# LPCB235_-_IO_Connector.net
KiCad netlist of a schematic drawn in Altium Designer
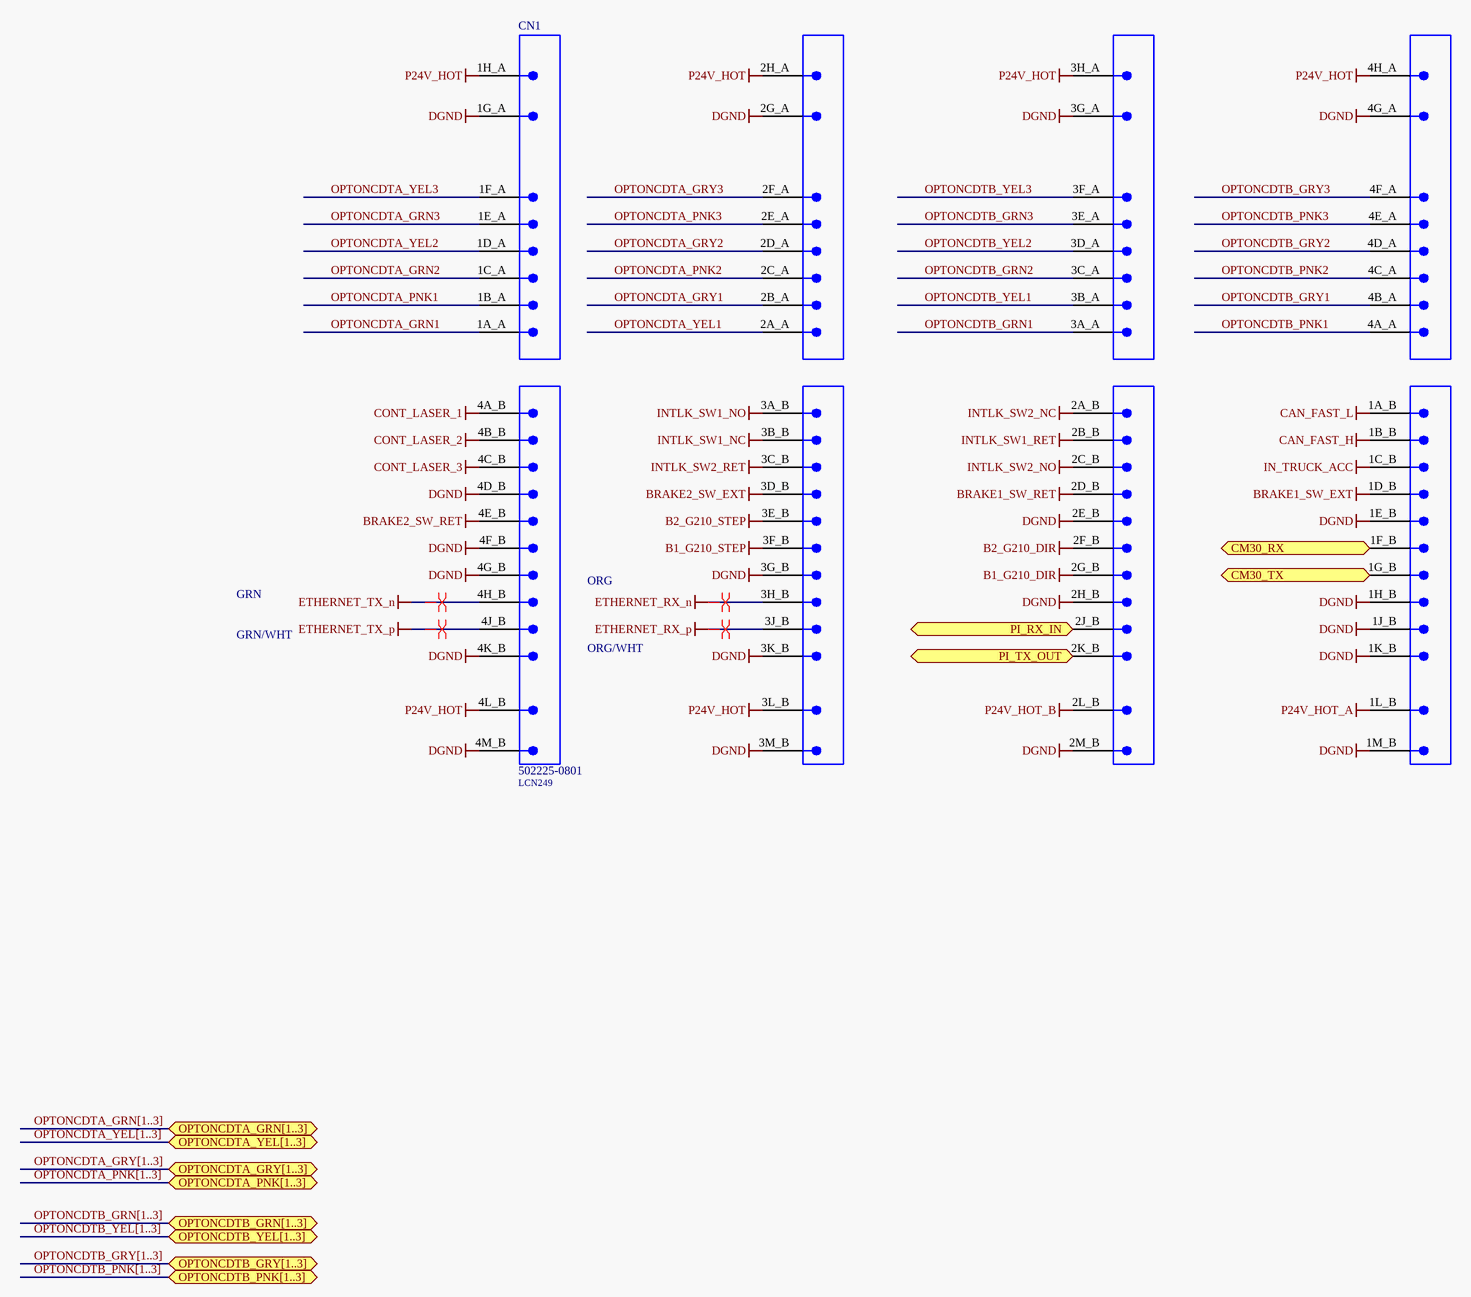
[diagram p0: LPCB235 - IO Connector.SchDoc]

(export (version "E")
  (design (tool "Eeschema 10.0.6"))
  (components
    (comp (ref "CN1")
      (value "502225-0801")
      (footprint "502225-0801")
      (description "Connector, Molex CMC, Automotive Socket, 80 Circuits, 2 Pockets")
      (fields (field (name "LDL_NUMBER") "LCN249"))
      (libsource (lib "LDL_Connectors") (part "502225-0801"))
    )
  )
  (nets
    (net (code "1") (name "/CM30_RX") (class "Default")
      (node (ref "CN1") (pin "1F_B") (pinfunction "1F_B_1F_B") (pintype "passive"))
    )
    (net (code "2") (name "/CM30_TX") (class "Default")
      (node (ref "CN1") (pin "1G_B") (pinfunction "1G_B_1G_B") (pintype "passive"))
    )
    (net (code "3") (name "/OPTONCDTA_GRN1") (class "Default")
      (node (ref "CN1") (pin "1A_A") (pinfunction "1A_1A_A") (pintype "passive"))
    )
    (net (code "4") (name "/OPTONCDTA_GRN2") (class "Default")
      (node (ref "CN1") (pin "1C_A") (pinfunction "1C_1C_A") (pintype "passive"))
    )
    (net (code "5") (name "/OPTONCDTA_GRN3") (class "Default")
      (node (ref "CN1") (pin "1E_A") (pinfunction "1E_1E_A") (pintype "passive"))
    )
    (net (code "7") (name "/OPTONCDTA_GRY1") (class "Default")
      (node (ref "CN1") (pin "2B_A") (pinfunction "2B_2B_A") (pintype "passive"))
    )
    (net (code "8") (name "/OPTONCDTA_GRY2") (class "Default")
      (node (ref "CN1") (pin "2D_A") (pinfunction "2D_2D_A") (pintype "passive"))
    )
    (net (code "9") (name "/OPTONCDTA_GRY3") (class "Default")
      (node (ref "CN1") (pin "2F_A") (pinfunction "2F_2F_A") (pintype "passive"))
    )
    (net (code "11") (name "/OPTONCDTA_PNK1") (class "Default")
      (node (ref "CN1") (pin "1B_A") (pinfunction "1B_1B_A") (pintype "passive"))
    )
    (net (code "12") (name "/OPTONCDTA_PNK2") (class "Default")
      (node (ref "CN1") (pin "2C_A") (pinfunction "2C_2C_A") (pintype "passive"))
    )
    (net (code "13") (name "/OPTONCDTA_PNK3") (class "Default")
      (node (ref "CN1") (pin "2E_A") (pinfunction "2E_2E_A") (pintype "passive"))
    )
    (net (code "15") (name "/OPTONCDTA_YEL1") (class "Default")
      (node (ref "CN1") (pin "2A_A") (pinfunction "2A_2A_A") (pintype "passive"))
    )
    (net (code "16") (name "/OPTONCDTA_YEL2") (class "Default")
      (node (ref "CN1") (pin "1D_A") (pinfunction "1D_1D_A") (pintype "passive"))
    )
    (net (code "17") (name "/OPTONCDTA_YEL3") (class "Default")
      (node (ref "CN1") (pin "1F_A") (pinfunction "1F_1F_A") (pintype "passive"))
    )
    (net (code "19") (name "/OPTONCDTB_GRN1") (class "Default")
      (node (ref "CN1") (pin "3A_A") (pinfunction "3A_3A_A") (pintype "passive"))
    )
    (net (code "20") (name "/OPTONCDTB_GRN2") (class "Default")
      (node (ref "CN1") (pin "3C_A") (pinfunction "3C_3C_A") (pintype "passive"))
    )
    (net (code "21") (name "/OPTONCDTB_GRN3") (class "Default")
      (node (ref "CN1") (pin "3E_A") (pinfunction "3E_3E_A") (pintype "passive"))
    )
    (net (code "23") (name "/OPTONCDTB_GRY1") (class "Default")
      (node (ref "CN1") (pin "4B_A") (pinfunction "4B_4B_A") (pintype "passive"))
    )
    (net (code "24") (name "/OPTONCDTB_GRY2") (class "Default")
      (node (ref "CN1") (pin "4D_A") (pinfunction "4D_4D_A") (pintype "passive"))
    )
    (net (code "25") (name "/OPTONCDTB_GRY3") (class "Default")
      (node (ref "CN1") (pin "4F_A") (pinfunction "4F_4F_A") (pintype "passive"))
    )
    (net (code "27") (name "/OPTONCDTB_PNK1") (class "Default")
      (node (ref "CN1") (pin "4A_A") (pinfunction "4A_4A_A") (pintype "passive"))
    )
    (net (code "28") (name "/OPTONCDTB_PNK2") (class "Default")
      (node (ref "CN1") (pin "4C_A") (pinfunction "4C_4C_A") (pintype "passive"))
    )
    (net (code "29") (name "/OPTONCDTB_PNK3") (class "Default")
      (node (ref "CN1") (pin "4E_A") (pinfunction "4E_4E_A") (pintype "passive"))
    )
    (net (code "31") (name "/OPTONCDTB_YEL1") (class "Default")
      (node (ref "CN1") (pin "3B_A") (pinfunction "3B_3B_A") (pintype "passive"))
    )
    (net (code "32") (name "/OPTONCDTB_YEL2") (class "Default")
      (node (ref "CN1") (pin "3D_A") (pinfunction "3D_3D_A") (pintype "passive"))
    )
    (net (code "33") (name "/OPTONCDTB_YEL3") (class "Default")
      (node (ref "CN1") (pin "3F_A") (pinfunction "3F_3F_A") (pintype "passive"))
    )
    (net (code "35") (name "/PI_RX_IN") (class "Default")
      (node (ref "CN1") (pin "2J_B") (pinfunction "2J_B_2J_B") (pintype "passive"))
    )
    (net (code "36") (name "/PI_TX_OUT") (class "Default")
      (node (ref "CN1") (pin "2K_B") (pinfunction "2K_B_2K_B") (pintype "passive"))
    )
    (net (code "37") (name "B1_G210_DIR") (class "Default")
      (node (ref "CN1") (pin "2G_B") (pinfunction "2G_B_2G_B") (pintype "passive"))
    )
    (net (code "38") (name "B1_G210_STEP") (class "Default")
      (node (ref "CN1") (pin "3F_B") (pinfunction "3F_B_3F_B") (pintype "passive"))
    )
    (net (code "39") (name "B2_G210_DIR") (class "Default")
      (node (ref "CN1") (pin "2F_B") (pinfunction "2F_B_2F_B") (pintype "passive"))
    )
    (net (code "40") (name "B2_G210_STEP") (class "Default")
      (node (ref "CN1") (pin "3E_B") (pinfunction "3E_B_3E_B") (pintype "passive"))
    )
    (net (code "41") (name "BRAKE1_SW_EXT") (class "Default")
      (node (ref "CN1") (pin "1D_B") (pinfunction "1D_B_1D_B") (pintype "passive"))
    )
    (net (code "42") (name "BRAKE1_SW_RET") (class "Default")
      (node (ref "CN1") (pin "2D_B") (pinfunction "2D_B_2D_B") (pintype "passive"))
    )
    (net (code "43") (name "BRAKE2_SW_EXT") (class "Default")
      (node (ref "CN1") (pin "3D_B") (pinfunction "3D_B_3D_B") (pintype "passive"))
    )
    (net (code "44") (name "BRAKE2_SW_RET") (class "Default")
      (node (ref "CN1") (pin "4E_B") (pinfunction "4E_B_4E_B") (pintype "passive"))
    )
    (net (code "45") (name "CAN_FAST_H") (class "Default")
      (node (ref "CN1") (pin "1B_B") (pinfunction "1B_B_1B_B") (pintype "passive"))
    )
    (net (code "46") (name "CAN_FAST_L") (class "Default")
      (node (ref "CN1") (pin "1A_B") (pinfunction "1A_B_1A_B") (pintype "passive"))
    )
    (net (code "47") (name "CONT_LASER_1") (class "Default")
      (node (ref "CN1") (pin "4A_B") (pinfunction "4A_B_4A_B") (pintype "passive"))
    )
    (net (code "48") (name "CONT_LASER_2") (class "Default")
      (node (ref "CN1") (pin "4B_B") (pinfunction "4B_B_4B_B") (pintype "passive"))
    )
    (net (code "49") (name "CONT_LASER_3") (class "Default")
      (node (ref "CN1") (pin "4C_B") (pinfunction "4C_B_4C_B") (pintype "passive"))
    )
    (net (code "50") (name "DGND") (class "Default")
      (node (ref "CN1") (pin "1E_B") (pinfunction "1E_B_1E_B") (pintype "passive"))
      (node (ref "CN1") (pin "1G_A") (pinfunction "1G_1G_A") (pintype "passive"))
      (node (ref "CN1") (pin "1H_B") (pinfunction "1H_B_1H_B") (pintype "passive"))
      (node (ref "CN1") (pin "1J_B") (pinfunction "1J_B_1J_B") (pintype "passive"))
      (node (ref "CN1") (pin "1K_B") (pinfunction "1K_B_1K_B") (pintype "passive"))
      (node (ref "CN1") (pin "1M_B") (pinfunction "1M_B_1M_B") (pintype "passive"))
      (node (ref "CN1") (pin "2E_B") (pinfunction "2E_B_2E_B") (pintype "passive"))
      (node (ref "CN1") (pin "2G_A") (pinfunction "2G_2G_A") (pintype "passive"))
      (node (ref "CN1") (pin "2H_B") (pinfunction "2H_B_2H_B") (pintype "passive"))
      (node (ref "CN1") (pin "2M_B") (pinfunction "2M_B_2M_B") (pintype "passive"))
      (node (ref "CN1") (pin "3G_A") (pinfunction "3G_3G_A") (pintype "passive"))
      (node (ref "CN1") (pin "3G_B") (pinfunction "3G_B_3G_B") (pintype "passive"))
      (node (ref "CN1") (pin "3K_B") (pinfunction "3K_B_3K_B") (pintype "passive"))
      (node (ref "CN1") (pin "3M_B") (pinfunction "3M_B_3M_B") (pintype "passive"))
      (node (ref "CN1") (pin "4D_B") (pinfunction "4D_B_4D_B") (pintype "passive"))
      (node (ref "CN1") (pin "4F_B") (pinfunction "4F_B_4F_B") (pintype "passive"))
      (node (ref "CN1") (pin "4G_A") (pinfunction "4G_4G_A") (pintype "passive"))
      (node (ref "CN1") (pin "4G_B") (pinfunction "4G_B_4G_B") (pintype "passive"))
      (node (ref "CN1") (pin "4K_B") (pinfunction "4K_B_4K_B") (pintype "passive"))
      (node (ref "CN1") (pin "4M_B") (pinfunction "4M_B_4M_B") (pintype "passive"))
    )
    (net (code "51") (name "ETHERNET_RX_n") (class "Default")
      (node (ref "CN1") (pin "3H_B") (pinfunction "3H_B_3H_B") (pintype "passive"))
    )
    (net (code "52") (name "ETHERNET_RX_p") (class "Default")
      (node (ref "CN1") (pin "3J_B") (pinfunction "3J_B_3J_B") (pintype "passive"))
    )
    (net (code "53") (name "ETHERNET_TX_n") (class "Default")
      (node (ref "CN1") (pin "4H_B") (pinfunction "4H_B_4H_B") (pintype "passive"))
    )
    (net (code "54") (name "ETHERNET_TX_p") (class "Default")
      (node (ref "CN1") (pin "4J_B") (pinfunction "4J_B_4J_B") (pintype "passive"))
    )
    (net (code "55") (name "INTLK_SW1_NC") (class "Default")
      (node (ref "CN1") (pin "3B_B") (pinfunction "3B_B_3B_B") (pintype "passive"))
    )
    (net (code "56") (name "INTLK_SW1_NO") (class "Default")
      (node (ref "CN1") (pin "3A_B") (pinfunction "3A_B_3A_B") (pintype "passive"))
    )
    (net (code "57") (name "INTLK_SW1_RET") (class "Default")
      (node (ref "CN1") (pin "2B_B") (pinfunction "2B_B_2B_B") (pintype "passive"))
    )
    (net (code "58") (name "INTLK_SW2_NC") (class "Default")
      (node (ref "CN1") (pin "2A_B") (pinfunction "2A_B_2A_B") (pintype "passive"))
    )
    (net (code "59") (name "INTLK_SW2_NO") (class "Default")
      (node (ref "CN1") (pin "2C_B") (pinfunction "2C_B_2C_B") (pintype "passive"))
    )
    (net (code "60") (name "INTLK_SW2_RET") (class "Default")
      (node (ref "CN1") (pin "3C_B") (pinfunction "3C_B_3C_B") (pintype "passive"))
    )
    (net (code "61") (name "IN_TRUCK_ACC") (class "Default")
      (node (ref "CN1") (pin "1C_B") (pinfunction "1C_B_1C_B") (pintype "passive"))
    )
    (net (code "62") (name "P24V_HOT") (class "Default")
      (node (ref "CN1") (pin "1H_A") (pinfunction "1H_1H_A") (pintype "passive"))
      (node (ref "CN1") (pin "2H_A") (pinfunction "2H_2H_A") (pintype "passive"))
      (node (ref "CN1") (pin "3H_A") (pinfunction "3H_3H_A") (pintype "passive"))
      (node (ref "CN1") (pin "3L_B") (pinfunction "3L_B_3L_B") (pintype "passive"))
      (node (ref "CN1") (pin "4H_A") (pinfunction "4H_4H_A") (pintype "passive"))
      (node (ref "CN1") (pin "4L_B") (pinfunction "4L_B_4L_B") (pintype "passive"))
    )
    (net (code "63") (name "P24V_HOT_A") (class "Default")
      (node (ref "CN1") (pin "1L_B") (pinfunction "1L_B_1L_B") (pintype "passive"))
    )
    (net (code "64") (name "P24V_HOT_B") (class "Default")
      (node (ref "CN1") (pin "2L_B") (pinfunction "2L_B_2L_B") (pintype "passive"))
    )
  )
)
